# attiniest85-batty-shield-mk-2_3.net
KiCad netlist of a schematic drawn in EAGLE
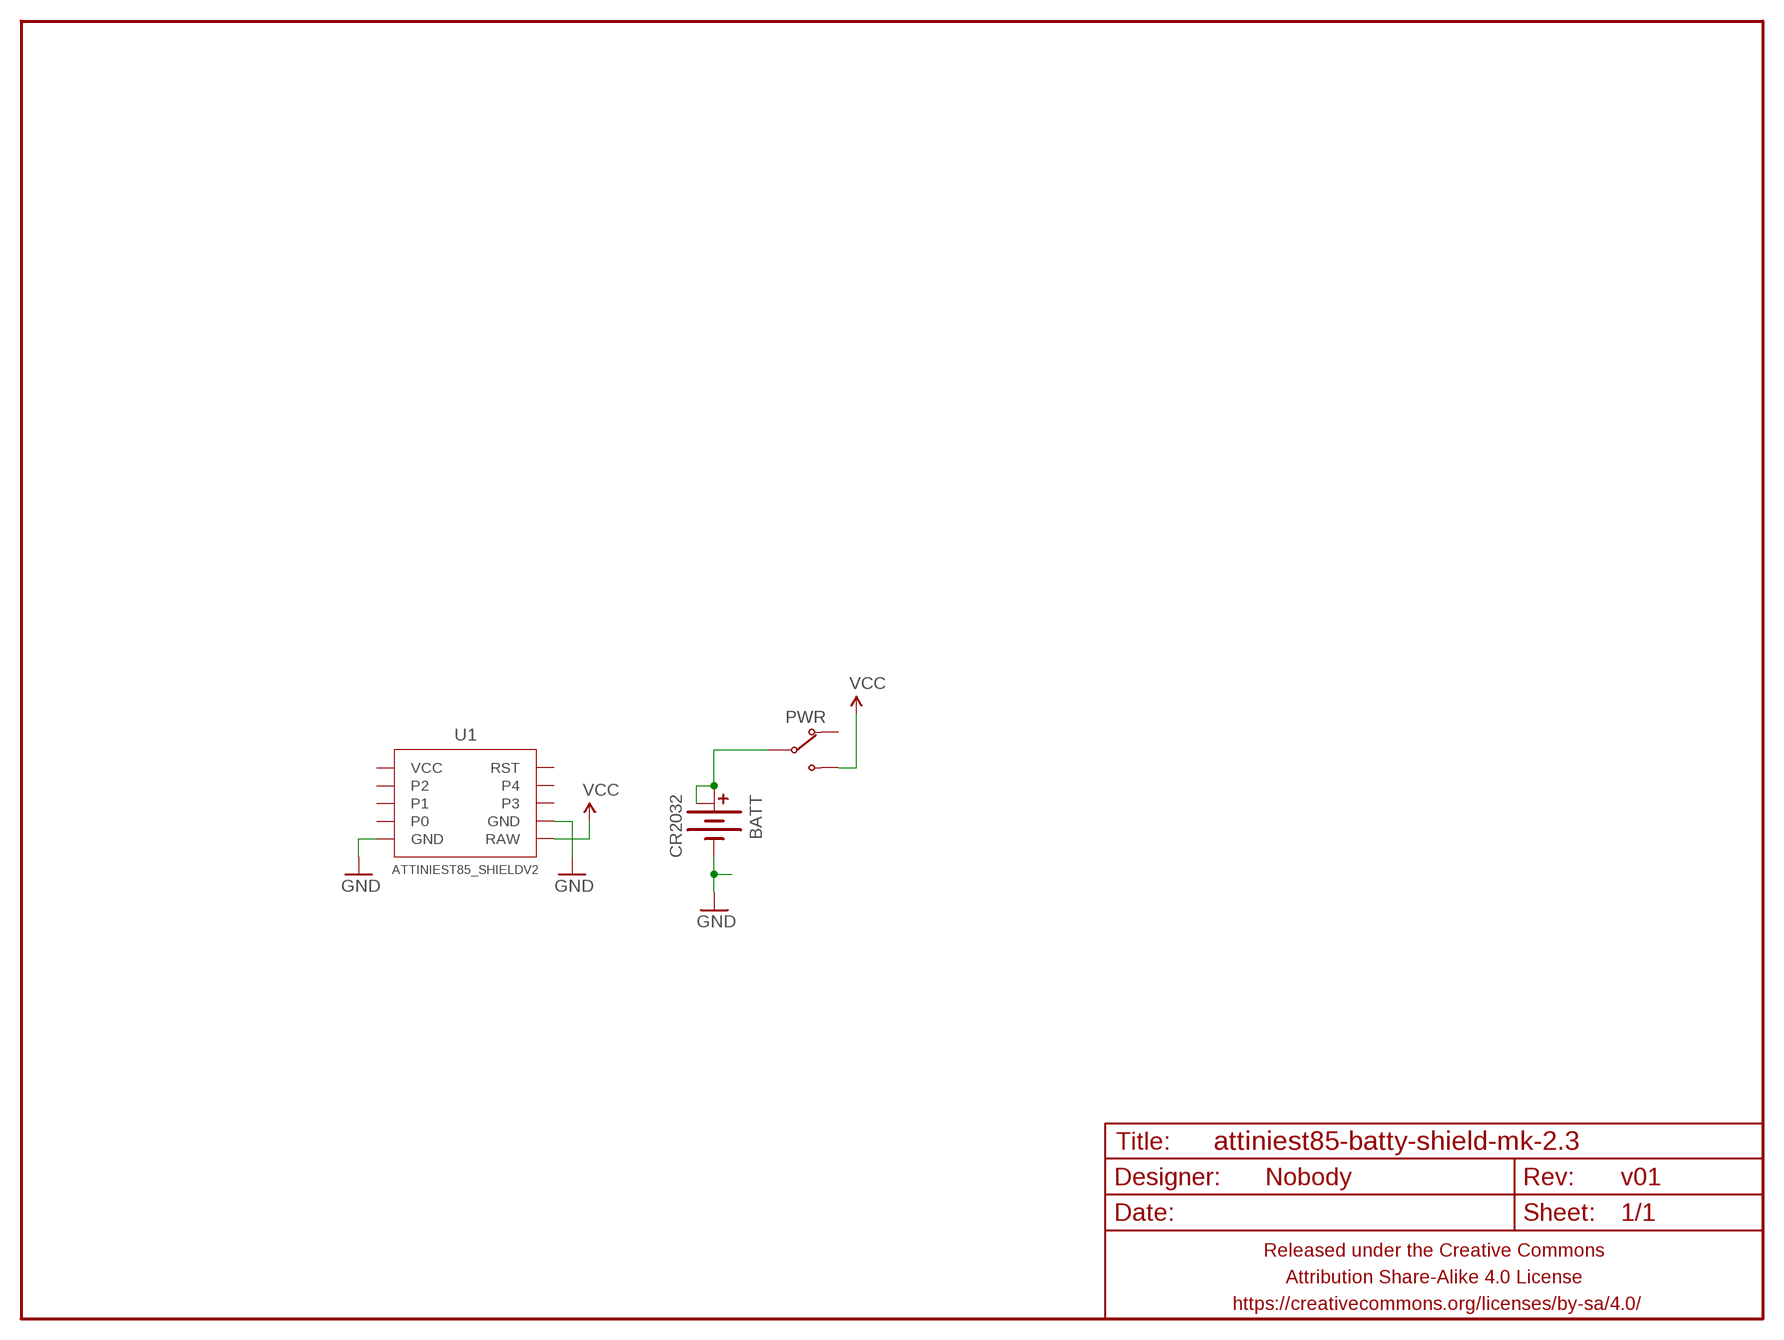
[diagram p0: schematic, sheet 1]

(export (version "E")
  (design (tool "Eeschema 10.0.6"))
  (components
    (comp (ref "BATT")
      (value "CR2032")
      (footprint "eagle-import:BATTCON_20MM_MINE")
      (libsource (lib "eagle-import") (part "BATTERY-COINCR2032_SMD"))
    )
    (comp (ref "FRAME1")
      (value "FRAME-LETTERNO_PACKAGE")
      (footprint "eagle-import:DUMMY")
      (fields (field (name "DESIGNER") "Nobody"))
      (libsource (lib "eagle-import") (part "FRAME-LETTERNO_PACKAGE"))
    )
    (comp (ref "PWR")
      (value "SWITCH-SPDTPTH-RA-2MM")
      (footprint "eagle-import:SPDT-RA-2MM")
      (libsource (lib "eagle-import") (part "SWITCH-SPDTPTH-RA-2MM"))
    )
    (comp (ref "U1")
      (value "ATTINIEST85_SHIELDV2")
      (footprint "eagle-import:ATTINIEST85_SHIELD_V2")
      (libsource (lib "eagle-import") (part "ATTINIEST85_SHIELDV2"))
    )
  )
  (nets
    (net (code "1") (name "GND") (class "Default")
      (node (ref "BATT") (pin "BOTTOM") (pinfunction "-_BOTTOM") (pintype "bidirectional"))
      (node (ref "U1") (pin "GND@1") (pinfunction "GND_GND@1") (pintype "bidirectional"))
      (node (ref "U1") (pin "GND@2") (pinfunction "GND_GND@2") (pintype "bidirectional"))
    )
    (net (code "2") (name "Net-(BATT-+)") (class "Default")
      (node (ref "BATT") (pin "TOP@1") (pinfunction "+_TOP@1") (pintype "bidirectional"))
      (node (ref "BATT") (pin "TOP@2") (pinfunction "+1_TOP@2") (pintype "bidirectional"))
      (node (ref "PWR") (pin "2") (pinfunction "COM_2") (pintype "passive"))
    )
    (net (code "3") (name "VCC") (class "Default")
      (node (ref "PWR") (pin "3") (pinfunction "NO_3") (pintype "passive"))
      (node (ref "U1") (pin "RAW") (pinfunction "RAW_RAW") (pintype "bidirectional"))
    )
    (net (code "4") (name "unconnected-(PWR-NC-Pad1)") (class "Default")
      (node (ref "PWR") (pin "1") (pinfunction "NC_1") (pintype "passive"))
    )
    (net (code "5") (name "unconnected-(U1-P0-Pad0)") (class "Default")
      (node (ref "U1") (pin "0") (pinfunction "P0_0") (pintype "bidirectional"))
    )
    (net (code "6") (name "unconnected-(U1-P1-Pad1)") (class "Default")
      (node (ref "U1") (pin "1") (pinfunction "P1_1") (pintype "bidirectional"))
    )
    (net (code "7") (name "unconnected-(U1-P2-Pad2)") (class "Default")
      (node (ref "U1") (pin "2") (pinfunction "P2_2") (pintype "bidirectional"))
    )
    (net (code "8") (name "unconnected-(U1-P3-Pad3)") (class "Default")
      (node (ref "U1") (pin "3") (pinfunction "P3_3") (pintype "bidirectional"))
    )
    (net (code "9") (name "unconnected-(U1-P4-Pad4)") (class "Default")
      (node (ref "U1") (pin "4") (pinfunction "P4_4") (pintype "bidirectional"))
    )
    (net (code "10") (name "unconnected-(U1-PadRST)") (class "Default")
      (node (ref "U1") (pin "RST") (pinfunction "RST_RST") (pintype "bidirectional"))
    )
    (net (code "11") (name "unconnected-(U1-PadVCC)") (class "Default")
      (node (ref "U1") (pin "VCC") (pinfunction "VCC_VCC") (pintype "bidirectional"))
    )
  )
)
